# CanBus25mar.net
KiCad netlist of a schematic drawn in EAGLE
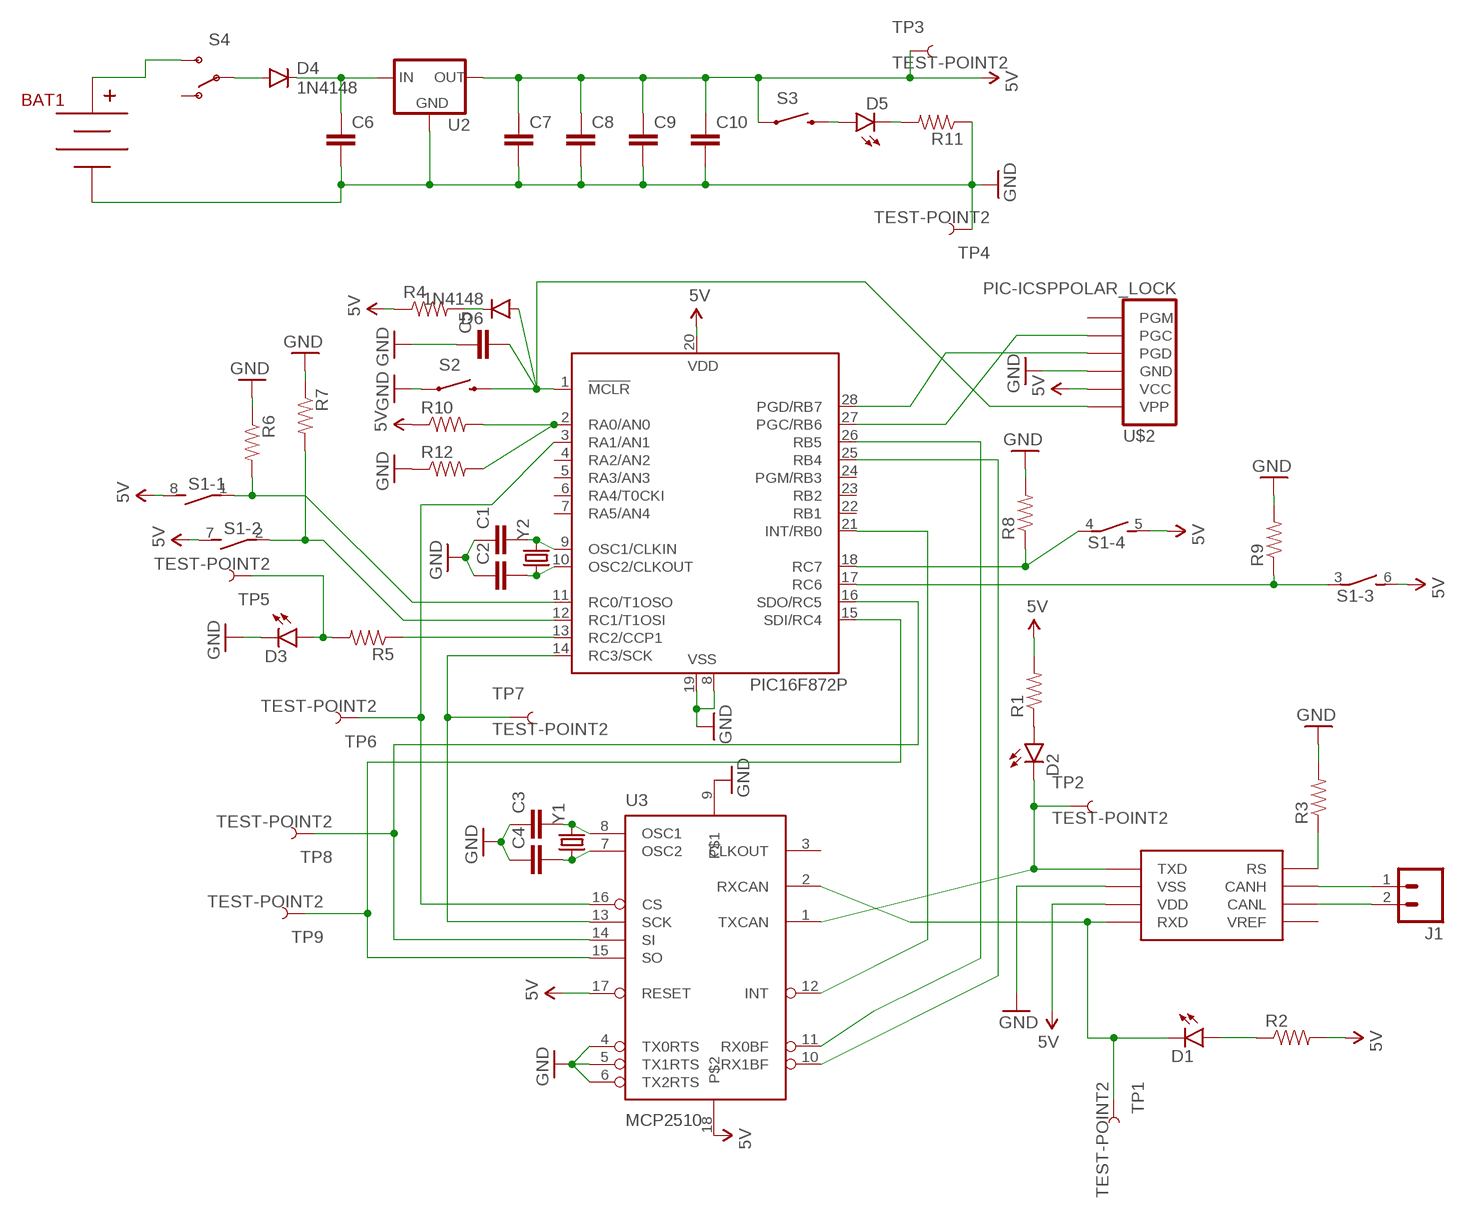
[diagram p0: schematic, sheet 1]

(export (version "E")
  (design (tool "Eeschema 10.0.6"))
  (components
    (comp (ref "BAT1")
      (value "BC9VPC")
      (footprint "eagle-import:BC9VPC")
      (libsource (lib "eagle-import") (part "BC9VPC"))
    )
    (comp (ref "C1")
      (value "CAPPTH")
      (footprint "eagle-import:CAP-PTH-SMALL")
      (libsource (lib "eagle-import") (part "CAPPTH"))
    )
    (comp (ref "C2")
      (value "CAPPTH")
      (footprint "eagle-import:CAP-PTH-SMALL")
      (libsource (lib "eagle-import") (part "CAPPTH"))
    )
    (comp (ref "C3")
      (value "CAPPTH")
      (footprint "eagle-import:CAP-PTH-SMALL")
      (libsource (lib "eagle-import") (part "CAPPTH"))
    )
    (comp (ref "C4")
      (value "CAPPTH")
      (footprint "eagle-import:CAP-PTH-SMALL")
      (libsource (lib "eagle-import") (part "CAPPTH"))
    )
    (comp (ref "C5")
      (value "CAPPTH")
      (footprint "eagle-import:CAP-PTH-SMALL")
      (libsource (lib "eagle-import") (part "CAPPTH"))
    )
    (comp (ref "C6")
      (value "CAPPTH")
      (footprint "eagle-import:CAP-PTH-SMALL")
      (libsource (lib "eagle-import") (part "CAPPTH"))
    )
    (comp (ref "C7")
      (value "CAPPTH")
      (footprint "eagle-import:CAP-PTH-SMALL")
      (libsource (lib "eagle-import") (part "CAPPTH"))
    )
    (comp (ref "C8")
      (value "CAPPTH")
      (footprint "eagle-import:CAP-PTH-SMALL")
      (libsource (lib "eagle-import") (part "CAPPTH"))
    )
    (comp (ref "C9")
      (value "CAPPTH")
      (footprint "eagle-import:CAP-PTH-SMALL")
      (libsource (lib "eagle-import") (part "CAPPTH"))
    )
    (comp (ref "C10")
      (value "CAPPTH")
      (footprint "eagle-import:CAP-PTH-SMALL")
      (libsource (lib "eagle-import") (part "CAPPTH"))
    )
    (comp (ref "D1")
      (value "LED5MM")
      (footprint "eagle-import:LED5MM")
      (libsource (lib "eagle-import") (part "LED5MM"))
    )
    (comp (ref "D2")
      (value "LED5MM")
      (footprint "eagle-import:LED5MM")
      (libsource (lib "eagle-import") (part "LED5MM"))
    )
    (comp (ref "D3")
      (value "LED5MM")
      (footprint "eagle-import:LED5MM")
      (libsource (lib "eagle-import") (part "LED5MM"))
    )
    (comp (ref "D4")
      (value "1N4148")
      (footprint "eagle-import:DIODE-1N4148-KIT")
      (libsource (lib "eagle-import") (part "DIODEKIT"))
    )
    (comp (ref "D5")
      (value "LED5MM")
      (footprint "eagle-import:LED5MM")
      (libsource (lib "eagle-import") (part "LED5MM"))
    )
    (comp (ref "D6")
      (value "1N4148")
      (footprint "eagle-import:DIODE-1N4148-KIT")
      (libsource (lib "eagle-import") (part "DIODEKIT"))
    )
    (comp (ref "IC1")
      (value "PIC16F872P")
      (footprint "eagle-import:DIL28-3")
      (fields (field (name "MF") "MICROCHIP") (field (name "MPN") "PIC16F872-I/SP"))
      (libsource (lib "eagle-import") (part "PIC16872PF"))
    )
    (comp (ref "J1")
      (value "M02PTH")
      (footprint "eagle-import:1X02")
      (libsource (lib "eagle-import") (part "M02PTH"))
    )
    (comp (ref "R1")
      (value "RESISTOREZ")
      (footprint "eagle-import:AXIAL-0.3EZ")
      (libsource (lib "eagle-import") (part "RESISTOREZ"))
    )
    (comp (ref "R2")
      (value "RESISTOREZ")
      (footprint "eagle-import:AXIAL-0.3EZ")
      (libsource (lib "eagle-import") (part "RESISTOREZ"))
    )
    (comp (ref "R3")
      (value "RESISTOREZ")
      (footprint "eagle-import:AXIAL-0.3EZ")
      (libsource (lib "eagle-import") (part "RESISTOREZ"))
    )
    (comp (ref "R4")
      (value "RESISTOREZ")
      (footprint "eagle-import:AXIAL-0.3EZ")
      (libsource (lib "eagle-import") (part "RESISTOREZ"))
    )
    (comp (ref "R5")
      (value "RESISTOREZ")
      (footprint "eagle-import:AXIAL-0.3EZ")
      (libsource (lib "eagle-import") (part "RESISTOREZ"))
    )
    (comp (ref "R6")
      (value "RESISTOREZ")
      (footprint "eagle-import:AXIAL-0.3EZ")
      (libsource (lib "eagle-import") (part "RESISTOREZ"))
    )
    (comp (ref "R7")
      (value "RESISTOREZ")
      (footprint "eagle-import:AXIAL-0.3EZ")
      (libsource (lib "eagle-import") (part "RESISTOREZ"))
    )
    (comp (ref "R8")
      (value "RESISTOREZ")
      (footprint "eagle-import:AXIAL-0.3EZ")
      (libsource (lib "eagle-import") (part "RESISTOREZ"))
    )
    (comp (ref "R9")
      (value "RESISTOREZ")
      (footprint "eagle-import:AXIAL-0.3EZ")
      (libsource (lib "eagle-import") (part "RESISTOREZ"))
    )
    (comp (ref "R10")
      (value "RESISTOREZ")
      (footprint "eagle-import:AXIAL-0.3EZ")
      (libsource (lib "eagle-import") (part "RESISTOREZ"))
    )
    (comp (ref "R11")
      (value "RESISTOREZ")
      (footprint "eagle-import:AXIAL-0.3EZ")
      (libsource (lib "eagle-import") (part "RESISTOREZ"))
    )
    (comp (ref "R12")
      (value "RESISTORAXIAL-0.3")
      (footprint "eagle-import:AXIAL-0.3")
      (libsource (lib "eagle-import") (part "SparkFun-Resistors_RESISTORAXIAL-0.3"))
    )
    (comp (ref "S1")
      (value "DIP04S")
      (footprint "eagle-import:DIP04S")
      (libsource (lib "eagle-import") (part "DIP04S"))
    )
    (comp (ref "S2")
      (value "SWITCH-MOMENTARY-2PTH")
      (footprint "eagle-import:TACTILE-PTH")
      (libsource (lib "eagle-import") (part "SWITCH-MOMENTARY-2PTH"))
    )
    (comp (ref "S3")
      (value "SWITCH-MOMENTARY-2PTH")
      (footprint "eagle-import:TACTILE-PTH")
      (libsource (lib "eagle-import") (part "SWITCH-MOMENTARY-2PTH"))
    )
    (comp (ref "S4")
      (value "SWITCH-SPDTKIT")
      (footprint "eagle-import:SWITCH-SPDT_KIT")
      (libsource (lib "eagle-import") (part "SWITCH-SPDTKIT"))
    )
    (comp (ref "TP1")
      (value "TEST-POINT2")
      (footprint "eagle-import:PAD.02X.02")
      (libsource (lib "eagle-import") (part "TEST-POINT2"))
    )
    (comp (ref "TP2")
      (value "TEST-POINT2")
      (footprint "eagle-import:PAD.02X.02")
      (libsource (lib "eagle-import") (part "TEST-POINT2"))
    )
    (comp (ref "TP3")
      (value "TEST-POINT2")
      (footprint "eagle-import:PAD.02X.02")
      (libsource (lib "eagle-import") (part "TEST-POINT2"))
    )
    (comp (ref "TP4")
      (value "TEST-POINT2")
      (footprint "eagle-import:PAD.02X.02")
      (libsource (lib "eagle-import") (part "TEST-POINT2"))
    )
    (comp (ref "TP5")
      (value "TEST-POINT2")
      (footprint "eagle-import:PAD.02X.02")
      (libsource (lib "eagle-import") (part "TEST-POINT2"))
    )
    (comp (ref "TP6")
      (value "TEST-POINT2")
      (footprint "eagle-import:PAD.02X.02")
      (libsource (lib "eagle-import") (part "TEST-POINT2"))
    )
    (comp (ref "TP7")
      (value "TEST-POINT2")
      (footprint "eagle-import:PAD.02X.02")
      (libsource (lib "eagle-import") (part "TEST-POINT2"))
    )
    (comp (ref "TP8")
      (value "TEST-POINT2")
      (footprint "eagle-import:PAD.02X.02")
      (libsource (lib "eagle-import") (part "TEST-POINT2"))
    )
    (comp (ref "TP9")
      (value "TEST-POINT2")
      (footprint "eagle-import:PAD.02X.02")
      (libsource (lib "eagle-import") (part "TEST-POINT2"))
    )
    (comp (ref "U$1")
      (value "MCP2551")
      (footprint "eagle-import:MCP2551")
      (libsource (lib "eagle-import") (part "MCP2551"))
    )
    (comp (ref "U$2")
      (value "PIC-ICSPPOLAR_LOCK")
      (footprint "eagle-import:MOLEX-1X6_LOCK")
      (libsource (lib "eagle-import") (part "PIC-ICSPPOLAR_LOCK"))
    )
    (comp (ref "U2")
      (value "V_REG_78XXSIDE")
      (footprint "eagle-import:78XXL")
      (libsource (lib "eagle-import") (part "V_REG_78XXSIDE"))
    )
    (comp (ref "U3")
      (value "MCP2510")
      (footprint "eagle-import:DIL18")
      (libsource (lib "eagle-import") (part "MCP2510"))
    )
    (comp (ref "Y1")
      (value "CRYSTALHC49UV")
      (footprint "eagle-import:HC49U-V")
      (libsource (lib "eagle-import") (part "CRYSTALHC49UV"))
    )
    (comp (ref "Y2")
      (value "CRYSTALHC49UV")
      (footprint "eagle-import:HC49U-V")
      (libsource (lib "eagle-import") (part "CRYSTALHC49UV"))
    )
  )
  (nets
    (net (code "1") (name "5V") (class "Default")
      (node (ref "C10") (pin "1") (pinfunction "1_1") (pintype "passive"))
      (node (ref "C7") (pin "1") (pinfunction "1_1") (pintype "passive"))
      (node (ref "C8") (pin "1") (pinfunction "1_1") (pintype "passive"))
      (node (ref "C9") (pin "1") (pinfunction "1_1") (pintype "passive"))
      (node (ref "IC1") (pin "20") (pinfunction "VDD_20") (pintype "power_in"))
      (node (ref "R1") (pin "P$2") (pinfunction "2_P$2") (pintype "passive"))
      (node (ref "R10") (pin "P$1") (pinfunction "1_P$1") (pintype "passive"))
      (node (ref "R2") (pin "P$2") (pinfunction "2_P$2") (pintype "passive"))
      (node (ref "R4") (pin "P$1") (pinfunction "1_P$1") (pintype "passive"))
      (node (ref "S1") (pin "5") (pinfunction "2_5") (pintype "passive"))
      (node (ref "S1") (pin "6") (pinfunction "2_6") (pintype "passive"))
      (node (ref "S1") (pin "7") (pinfunction "2_7") (pintype "passive"))
      (node (ref "S1") (pin "8") (pinfunction "2_8") (pintype "passive"))
      (node (ref "S3") (pin "1") (pinfunction "1_1") (pintype "passive"))
      (node (ref "TP3") (pin "P$1") (pinfunction "1_P$1") (pintype "bidirectional"))
      (node (ref "U$1") (pin "VDD") (pinfunction "VDD_VDD") (pintype "bidirectional"))
      (node (ref "U$2") (pin "5") (pinfunction "VCC_5") (pintype "bidirectional"))
      (node (ref "U2") (pin "OUT") (pinfunction "OUT_OUT") (pintype "passive"))
      (node (ref "U3") (pin "17") (pinfunction "RESET_17") (pintype "input"))
      (node (ref "U3") (pin "18") (pinfunction "P$2_18") (pintype "bidirectional"))
    )
    (net (code "2") (name "GND") (class "Default")
      (node (ref "BAT1") (pin "V-") (pinfunction "V-_V-") (pintype "bidirectional"))
      (node (ref "C1") (pin "1") (pinfunction "1_1") (pintype "passive"))
      (node (ref "C10") (pin "2") (pinfunction "2_2") (pintype "passive"))
      (node (ref "C2") (pin "1") (pinfunction "1_1") (pintype "passive"))
      (node (ref "C3") (pin "1") (pinfunction "1_1") (pintype "passive"))
      (node (ref "C4") (pin "1") (pinfunction "1_1") (pintype "passive"))
      (node (ref "C5") (pin "1") (pinfunction "1_1") (pintype "passive"))
      (node (ref "C6") (pin "2") (pinfunction "2_2") (pintype "passive"))
      (node (ref "C7") (pin "2") (pinfunction "2_2") (pintype "passive"))
      (node (ref "C8") (pin "2") (pinfunction "2_2") (pintype "passive"))
      (node (ref "C9") (pin "2") (pinfunction "2_2") (pintype "passive"))
      (node (ref "D3") (pin "K") (pinfunction "C_K") (pintype "passive"))
      (node (ref "IC1") (pin "19") (pinfunction "VSS_19") (pintype "power_in"))
      (node (ref "IC1") (pin "8") (pinfunction "VSS_8") (pintype "power_in"))
      (node (ref "R11") (pin "P$1") (pinfunction "1_P$1") (pintype "passive"))
      (node (ref "R12") (pin "P$1") (pinfunction "1_P$1") (pintype "passive"))
      (node (ref "R3") (pin "P$2") (pinfunction "2_P$2") (pintype "passive"))
      (node (ref "R6") (pin "P$1") (pinfunction "1_P$1") (pintype "passive"))
      (node (ref "R7") (pin "P$1") (pinfunction "1_P$1") (pintype "passive"))
      (node (ref "R8") (pin "P$2") (pinfunction "2_P$2") (pintype "passive"))
      (node (ref "R9") (pin "P$2") (pinfunction "2_P$2") (pintype "passive"))
      (node (ref "S2") (pin "1") (pinfunction "1_1") (pintype "passive"))
      (node (ref "TP4") (pin "P$1") (pinfunction "1_P$1") (pintype "bidirectional"))
      (node (ref "U$1") (pin "VSS") (pinfunction "VSS_VSS") (pintype "bidirectional"))
      (node (ref "U$2") (pin "4") (pinfunction "GND_4") (pintype "bidirectional"))
      (node (ref "U2") (pin "GND") (pinfunction "GND_GND") (pintype "input"))
      (node (ref "U3") (pin "4") (pinfunction "TX0RTS_4") (pintype "input"))
      (node (ref "U3") (pin "5") (pinfunction "TX1RTS_5") (pintype "input"))
      (node (ref "U3") (pin "6") (pinfunction "TX2RTS_6") (pintype "input"))
      (node (ref "U3") (pin "9") (pinfunction "P$1_9") (pintype "bidirectional"))
    )
    (net (code "3") (name "Net-(C6-Pad1)") (class "Default")
      (node (ref "C6") (pin "1") (pinfunction "1_1") (pintype "passive"))
      (node (ref "D4") (pin "C") (pinfunction "C_C") (pintype "passive"))
      (node (ref "U2") (pin "IN") (pinfunction "IN_IN") (pintype "input"))
    )
    (net (code "4") (name "Net-(D1-C)") (class "Default")
      (node (ref "D1") (pin "K") (pinfunction "C_K") (pintype "passive"))
      (node (ref "TP1") (pin "P$1") (pinfunction "1_P$1") (pintype "bidirectional"))
      (node (ref "U$1") (pin "RXD") (pinfunction "RXD_RXD") (pintype "bidirectional"))
      (node (ref "U3") (pin "2") (pinfunction "RXCAN_2") (pintype "input"))
    )
    (net (code "5") (name "Net-(D2-C)") (class "Default")
      (node (ref "D2") (pin "K") (pinfunction "C_K") (pintype "passive"))
      (node (ref "TP2") (pin "P$1") (pinfunction "1_P$1") (pintype "bidirectional"))
      (node (ref "U$1") (pin "TXD") (pinfunction "TXD_TXD") (pintype "bidirectional"))
      (node (ref "U3") (pin "1") (pinfunction "TXCAN_1") (pintype "output"))
    )
    (net (code "6") (name "Net-(D5-C)") (class "Default")
      (node (ref "D5") (pin "K") (pinfunction "C_K") (pintype "passive"))
      (node (ref "R11") (pin "P$2") (pinfunction "2_P$2") (pintype "passive"))
    )
    (net (code "7") (name "Net-(IC1-INT{slash}RB0)") (class "Default")
      (node (ref "IC1") (pin "21") (pinfunction "INT/RB0_21") (pintype "bidirectional"))
      (node (ref "U3") (pin "12") (pinfunction "INT_12") (pintype "output"))
    )
    (net (code "8") (name "Net-(IC1-OSC1{slash}CLKIN)") (class "Default")
      (node (ref "C1") (pin "2") (pinfunction "2_2") (pintype "passive"))
      (node (ref "IC1") (pin "9") (pinfunction "OSC1/CLKIN_9") (pintype "input"))
      (node (ref "Y2") (pin "2") (pinfunction "2_2") (pintype "passive"))
    )
    (net (code "9") (name "Net-(IC1-OSC2{slash}CLKOUT)") (class "Default")
      (node (ref "C2") (pin "2") (pinfunction "2_2") (pintype "passive"))
      (node (ref "IC1") (pin "10") (pinfunction "OSC2/CLKOUT_10") (pintype "output"))
      (node (ref "Y2") (pin "1") (pinfunction "1_1") (pintype "passive"))
    )
    (net (code "10") (name "Net-(IC1-PGC{slash}RB6)") (class "Default")
      (node (ref "IC1") (pin "27") (pinfunction "PGC/RB6_27") (pintype "bidirectional"))
      (node (ref "U$2") (pin "2") (pinfunction "PGC_2") (pintype "bidirectional"))
    )
    (net (code "11") (name "Net-(IC1-PGD{slash}RB7)") (class "Default")
      (node (ref "IC1") (pin "28") (pinfunction "PGD/RB7_28") (pintype "bidirectional"))
      (node (ref "U$2") (pin "3") (pinfunction "PGD_3") (pintype "bidirectional"))
    )
    (net (code "12") (name "Net-(IC1-RA0{slash}AN0)") (class "Default")
      (node (ref "IC1") (pin "2") (pinfunction "RA0/AN0_2") (pintype "bidirectional"))
      (node (ref "R10") (pin "P$2") (pinfunction "2_P$2") (pintype "passive"))
      (node (ref "R12") (pin "P$2") (pinfunction "2_P$2") (pintype "passive"))
    )
    (net (code "13") (name "Net-(IC1-RA1{slash}AN1)") (class "Default")
      (node (ref "IC1") (pin "3") (pinfunction "RA1/AN1_3") (pintype "bidirectional"))
      (node (ref "TP6") (pin "P$1") (pinfunction "1_P$1") (pintype "bidirectional"))
      (node (ref "U3") (pin "16") (pinfunction "CS_16") (pintype "input"))
    )
    (net (code "14") (name "Net-(IC1-RB4)") (class "Default")
      (node (ref "IC1") (pin "25") (pinfunction "RB4_25") (pintype "bidirectional"))
      (node (ref "U3") (pin "10") (pinfunction "RX1BF_10") (pintype "output"))
    )
    (net (code "15") (name "Net-(IC1-RB5)") (class "Default")
      (node (ref "IC1") (pin "26") (pinfunction "RB5_26") (pintype "bidirectional"))
      (node (ref "U3") (pin "11") (pinfunction "RX0BF_11") (pintype "output"))
    )
    (net (code "16") (name "Net-(IC1-RC0{slash}T1OSO)") (class "Default")
      (node (ref "IC1") (pin "11") (pinfunction "RC0/T1OSO_11") (pintype "bidirectional"))
      (node (ref "R6") (pin "P$2") (pinfunction "2_P$2") (pintype "passive"))
      (node (ref "S1") (pin "1") (pinfunction "1_1") (pintype "passive"))
    )
    (net (code "17") (name "Net-(IC1-RC1{slash}T1OSI)") (class "Default")
      (node (ref "IC1") (pin "12") (pinfunction "RC1/T1OSI_12") (pintype "bidirectional"))
      (node (ref "R7") (pin "P$2") (pinfunction "2_P$2") (pintype "passive"))
      (node (ref "S1") (pin "2") (pinfunction "1_2") (pintype "passive"))
    )
    (net (code "18") (name "Net-(IC1-RC2{slash}CCP1)") (class "Default")
      (node (ref "IC1") (pin "13") (pinfunction "RC2/CCP1_13") (pintype "bidirectional"))
      (node (ref "R5") (pin "P$1") (pinfunction "1_P$1") (pintype "passive"))
    )
    (net (code "19") (name "Net-(IC1-RC3{slash}SCK)") (class "Default")
      (node (ref "IC1") (pin "14") (pinfunction "RC3/SCK_14") (pintype "bidirectional"))
      (node (ref "TP7") (pin "P$1") (pinfunction "1_P$1") (pintype "bidirectional"))
      (node (ref "U3") (pin "13") (pinfunction "SCK_13") (pintype "input"))
    )
    (net (code "20") (name "Net-(IC1-RC6)") (class "Default")
      (node (ref "IC1") (pin "17") (pinfunction "RC6_17") (pintype "bidirectional"))
      (node (ref "R9") (pin "P$1") (pinfunction "1_P$1") (pintype "passive"))
      (node (ref "S1") (pin "3") (pinfunction "1_3") (pintype "passive"))
    )
    (net (code "21") (name "Net-(IC1-RC7)") (class "Default")
      (node (ref "IC1") (pin "18") (pinfunction "RC7_18") (pintype "bidirectional"))
      (node (ref "R8") (pin "P$1") (pinfunction "1_P$1") (pintype "passive"))
      (node (ref "S1") (pin "4") (pinfunction "1_4") (pintype "passive"))
    )
    (net (code "22") (name "Net-(IC1-SDI{slash}RC4)") (class "Default")
      (node (ref "IC1") (pin "15") (pinfunction "SDI/RC4_15") (pintype "bidirectional"))
      (node (ref "TP9") (pin "P$1") (pinfunction "1_P$1") (pintype "bidirectional"))
      (node (ref "U3") (pin "15") (pinfunction "SO_15") (pintype "output"))
    )
    (net (code "23") (name "Net-(IC1-SDO{slash}RC5)") (class "Default")
      (node (ref "IC1") (pin "16") (pinfunction "SDO/RC5_16") (pintype "bidirectional"))
      (node (ref "TP8") (pin "P$1") (pinfunction "1_P$1") (pintype "bidirectional"))
      (node (ref "U3") (pin "14") (pinfunction "SI_14") (pintype "input"))
    )
    (net (code "24") (name "Net-(IC1-~{MCLR})") (class "Default")
      (node (ref "C5") (pin "2") (pinfunction "2_2") (pintype "passive"))
      (node (ref "D6") (pin "A") (pinfunction "A_A") (pintype "passive"))
      (node (ref "IC1") (pin "1") (pinfunction "~{MCLR}_1") (pintype "input"))
      (node (ref "S2") (pin "3") (pinfunction "2_3") (pintype "passive"))
      (node (ref "U$2") (pin "6") (pinfunction "VPP_6") (pintype "bidirectional"))
    )
    (net (code "25") (name "Net-(J1-Pad1)") (class "Default")
      (node (ref "J1") (pin "1") (pinfunction "1_1") (pintype "passive"))
      (node (ref "U$1") (pin "CANH") (pinfunction "CANH_CANH") (pintype "bidirectional"))
    )
    (net (code "26") (name "Net-(J1-Pad2)") (class "Default")
      (node (ref "J1") (pin "2") (pinfunction "2_2") (pintype "passive"))
      (node (ref "U$1") (pin "CANL") (pinfunction "CANL_CANL") (pintype "bidirectional"))
    )
    (net (code "27") (name "Net-(R1-1)") (class "Default")
      (node (ref "D2") (pin "A") (pinfunction "A_A") (pintype "passive"))
      (node (ref "R1") (pin "P$1") (pinfunction "1_P$1") (pintype "passive"))
    )
    (net (code "28") (name "Net-(R2-1)") (class "Default")
      (node (ref "D1") (pin "A") (pinfunction "A_A") (pintype "passive"))
      (node (ref "R2") (pin "P$1") (pinfunction "1_P$1") (pintype "passive"))
    )
    (net (code "29") (name "Net-(R3-1)") (class "Default")
      (node (ref "R3") (pin "P$1") (pinfunction "1_P$1") (pintype "passive"))
      (node (ref "U$1") (pin "RS") (pinfunction "RS_RS") (pintype "bidirectional"))
    )
    (net (code "30") (name "Net-(R4-2)") (class "Default")
      (node (ref "D6") (pin "C") (pinfunction "C_C") (pintype "passive"))
      (node (ref "R4") (pin "P$2") (pinfunction "2_P$2") (pintype "passive"))
    )
    (net (code "31") (name "Net-(R5-2)") (class "Default")
      (node (ref "D3") (pin "A") (pinfunction "A_A") (pintype "passive"))
      (node (ref "R5") (pin "P$2") (pinfunction "2_P$2") (pintype "passive"))
      (node (ref "TP5") (pin "P$1") (pinfunction "1_P$1") (pintype "bidirectional"))
    )
    (net (code "32") (name "Net-(S3-2)") (class "Default")
      (node (ref "D5") (pin "A") (pinfunction "A_A") (pintype "passive"))
      (node (ref "S3") (pin "3") (pinfunction "2_3") (pintype "passive"))
    )
    (net (code "33") (name "Net-(S4-P)") (class "Default")
      (node (ref "D4") (pin "A") (pinfunction "A_A") (pintype "passive"))
      (node (ref "S4") (pin "2") (pinfunction "P_2") (pintype "passive"))
    )
    (net (code "34") (name "Net-(S4-S)") (class "Default")
      (node (ref "BAT1") (pin "V+") (pinfunction "V+_V+") (pintype "bidirectional"))
      (node (ref "S4") (pin "3") (pinfunction "S_3") (pintype "passive"))
    )
    (net (code "35") (name "Net-(U3-OSC1)") (class "Default")
      (node (ref "C3") (pin "2") (pinfunction "2_2") (pintype "passive"))
      (node (ref "U3") (pin "8") (pinfunction "OSC1_8") (pintype "input"))
      (node (ref "Y1") (pin "2") (pinfunction "2_2") (pintype "passive"))
    )
    (net (code "36") (name "Net-(U3-OSC2)") (class "Default")
      (node (ref "C4") (pin "2") (pinfunction "2_2") (pintype "passive"))
      (node (ref "U3") (pin "7") (pinfunction "OSC2_7") (pintype "output"))
      (node (ref "Y1") (pin "1") (pinfunction "1_1") (pintype "passive"))
    )
    (net (code "37") (name "unconnected-(IC1-PGM{slash}RB3-Pad24)") (class "Default")
      (node (ref "IC1") (pin "24") (pinfunction "PGM/RB3_24") (pintype "bidirectional"))
    )
    (net (code "38") (name "unconnected-(IC1-RA2{slash}AN2-Pad4)") (class "Default")
      (node (ref "IC1") (pin "4") (pinfunction "RA2/AN2_4") (pintype "bidirectional"))
    )
    (net (code "39") (name "unconnected-(IC1-RA3{slash}AN3-Pad5)") (class "Default")
      (node (ref "IC1") (pin "5") (pinfunction "RA3/AN3_5") (pintype "bidirectional"))
    )
    (net (code "40") (name "unconnected-(IC1-RA4{slash}T0CKI-Pad6)") (class "Default")
      (node (ref "IC1") (pin "6") (pinfunction "RA4/T0CKI_6") (pintype "bidirectional"))
    )
    (net (code "41") (name "unconnected-(IC1-RA5{slash}AN4-Pad7)") (class "Default")
      (node (ref "IC1") (pin "7") (pinfunction "RA5/AN4_7") (pintype "bidirectional"))
    )
    (net (code "42") (name "unconnected-(IC1-RB1-Pad22)") (class "Default")
      (node (ref "IC1") (pin "22") (pinfunction "RB1_22") (pintype "bidirectional"))
    )
    (net (code "43") (name "unconnected-(IC1-RB2-Pad23)") (class "Default")
      (node (ref "IC1") (pin "23") (pinfunction "RB2_23") (pintype "bidirectional"))
    )
    (net (code "44") (name "unconnected-(S4-O-Pad1)") (class "Default")
      (node (ref "S4") (pin "1") (pinfunction "O_1") (pintype "passive"))
    )
    (net (code "45") (name "unconnected-(U$1-PadVREF)") (class "Default")
      (node (ref "U$1") (pin "VREF") (pinfunction "VREF_VREF") (pintype "bidirectional"))
    )
    (net (code "46") (name "unconnected-(U$2-PGM-Pad1)") (class "Default")
      (node (ref "U$2") (pin "1") (pinfunction "PGM_1") (pintype "bidirectional"))
    )
    (net (code "47") (name "unconnected-(U3-CLKOUT-Pad3)") (class "Default")
      (node (ref "U3") (pin "3") (pinfunction "CLKOUT_3") (pintype "output"))
    )
  )
)
